# irBoard_mirror.net
KiCad netlist of a schematic drawn in EAGLE
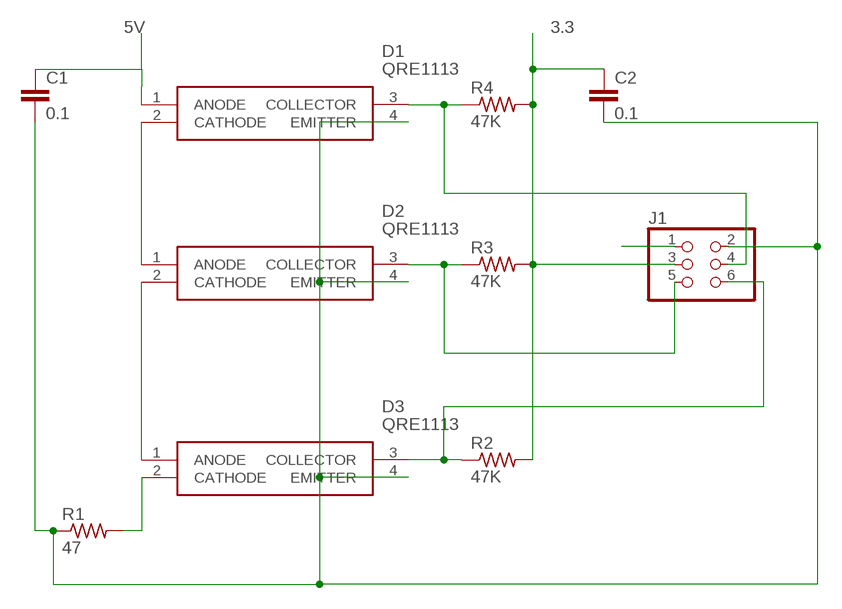
[diagram p0: schematic, sheet 1]

(export (version "E")
  (design (tool "Eeschema 10.0.6"))
  (components
    (comp (ref "C1")
      (value "0.1")
      (footprint "eagle-import:C025-024X044")
      (libsource (lib "eagle-import") (part "C-EU025-024X044"))
    )
    (comp (ref "C2")
      (value "0.1")
      (footprint "eagle-import:C025-024X044")
      (libsource (lib "eagle-import") (part "C-EU025-024X044"))
    )
    (comp (ref "D1")
      (value "QRE1113")
      (footprint "eagle-import:QRE1113")
      (fields (field (name "RS_PART_NUMBER") "8629400"))
      (libsource (lib "eagle-import") (part "QRE1113"))
    )
    (comp (ref "D2")
      (value "QRE1113")
      (footprint "eagle-import:QRE1113")
      (fields (field (name "RS_PART_NUMBER") "8629400"))
      (libsource (lib "eagle-import") (part "QRE1113"))
    )
    (comp (ref "D3")
      (value "QRE1113")
      (footprint "eagle-import:QRE1113")
      (fields (field (name "RS_PART_NUMBER") "8629400"))
      (libsource (lib "eagle-import") (part "QRE1113"))
    )
    (comp (ref "J1")
      (value "PINHD-2X3")
      (footprint "eagle-import:2X03")
      (libsource (lib "eagle-import") (part "PINHD-2X3"))
    )
    (comp (ref "R1")
      (value "47")
      (footprint "eagle-import:0204_5")
      (libsource (lib "eagle-import") (part "R-US_0204/5"))
    )
    (comp (ref "R2")
      (value "47K")
      (footprint "eagle-import:0204_5")
      (libsource (lib "eagle-import") (part "R-US_0204/5"))
    )
    (comp (ref "R3")
      (value "47K")
      (footprint "eagle-import:0204_5")
      (libsource (lib "eagle-import") (part "R-US_0204/5"))
    )
    (comp (ref "R4")
      (value "47K")
      (footprint "eagle-import:0204_5")
      (libsource (lib "eagle-import") (part "R-US_0204/5"))
    )
  )
  (nets
    (net (code "1") (name "/3.3") (class "Default")
      (node (ref "C2") (pin "1") (pinfunction "1_1") (pintype "passive"))
      (node (ref "J1") (pin "3") (pinfunction "3_3") (pintype "passive"))
      (node (ref "R2") (pin "2") (pinfunction "2_2") (pintype "passive"))
      (node (ref "R3") (pin "2") (pinfunction "2_2") (pintype "passive"))
      (node (ref "R4") (pin "2") (pinfunction "2_2") (pintype "passive"))
    )
    (net (code "2") (name "/5V") (class "Default")
      (node (ref "C1") (pin "1") (pinfunction "1_1") (pintype "passive"))
      (node (ref "D1") (pin "1") (pinfunction "ANODE_1") (pintype "power_in"))
      (node (ref "J1") (pin "1") (pinfunction "1_1") (pintype "passive"))
    )
    (net (code "3") (name "Net-(D1-CATHODE)") (class "Default")
      (node (ref "D1") (pin "2") (pinfunction "CATHODE_2") (pintype "power_in"))
      (node (ref "D2") (pin "1") (pinfunction "ANODE_1") (pintype "power_in"))
    )
    (net (code "4") (name "Net-(D1-COLLECTOR)") (class "Default")
      (node (ref "D1") (pin "3") (pinfunction "COLLECTOR_3") (pintype "input"))
      (node (ref "J1") (pin "4") (pinfunction "4_4") (pintype "passive"))
      (node (ref "R4") (pin "1") (pinfunction "1_1") (pintype "passive"))
    )
    (net (code "5") (name "Net-(D1-EMITTER)") (class "Default")
      (node (ref "C1") (pin "2") (pinfunction "2_2") (pintype "passive"))
      (node (ref "C2") (pin "2") (pinfunction "2_2") (pintype "passive"))
      (node (ref "D1") (pin "4") (pinfunction "EMITTER_4") (pintype "output"))
      (node (ref "D2") (pin "4") (pinfunction "EMITTER_4") (pintype "output"))
      (node (ref "D3") (pin "4") (pinfunction "EMITTER_4") (pintype "output"))
      (node (ref "J1") (pin "2") (pinfunction "2_2") (pintype "passive"))
      (node (ref "R1") (pin "1") (pinfunction "1_1") (pintype "passive"))
    )
    (net (code "6") (name "Net-(D2-CATHODE)") (class "Default")
      (node (ref "D2") (pin "2") (pinfunction "CATHODE_2") (pintype "power_in"))
      (node (ref "D3") (pin "1") (pinfunction "ANODE_1") (pintype "power_in"))
    )
    (net (code "7") (name "Net-(D2-COLLECTOR)") (class "Default")
      (node (ref "D2") (pin "3") (pinfunction "COLLECTOR_3") (pintype "input"))
      (node (ref "J1") (pin "5") (pinfunction "5_5") (pintype "passive"))
      (node (ref "R3") (pin "1") (pinfunction "1_1") (pintype "passive"))
    )
    (net (code "8") (name "Net-(D3-CATHODE)") (class "Default")
      (node (ref "D3") (pin "2") (pinfunction "CATHODE_2") (pintype "power_in"))
      (node (ref "R1") (pin "2") (pinfunction "2_2") (pintype "passive"))
    )
    (net (code "9") (name "Net-(D3-COLLECTOR)") (class "Default")
      (node (ref "D3") (pin "3") (pinfunction "COLLECTOR_3") (pintype "input"))
      (node (ref "J1") (pin "6") (pinfunction "6_6") (pintype "passive"))
      (node (ref "R2") (pin "1") (pinfunction "1_1") (pintype "passive"))
    )
  )
)
